# VL53L1X_Winkelplatine.net
KiCad netlist of a schematic drawn in EAGLE
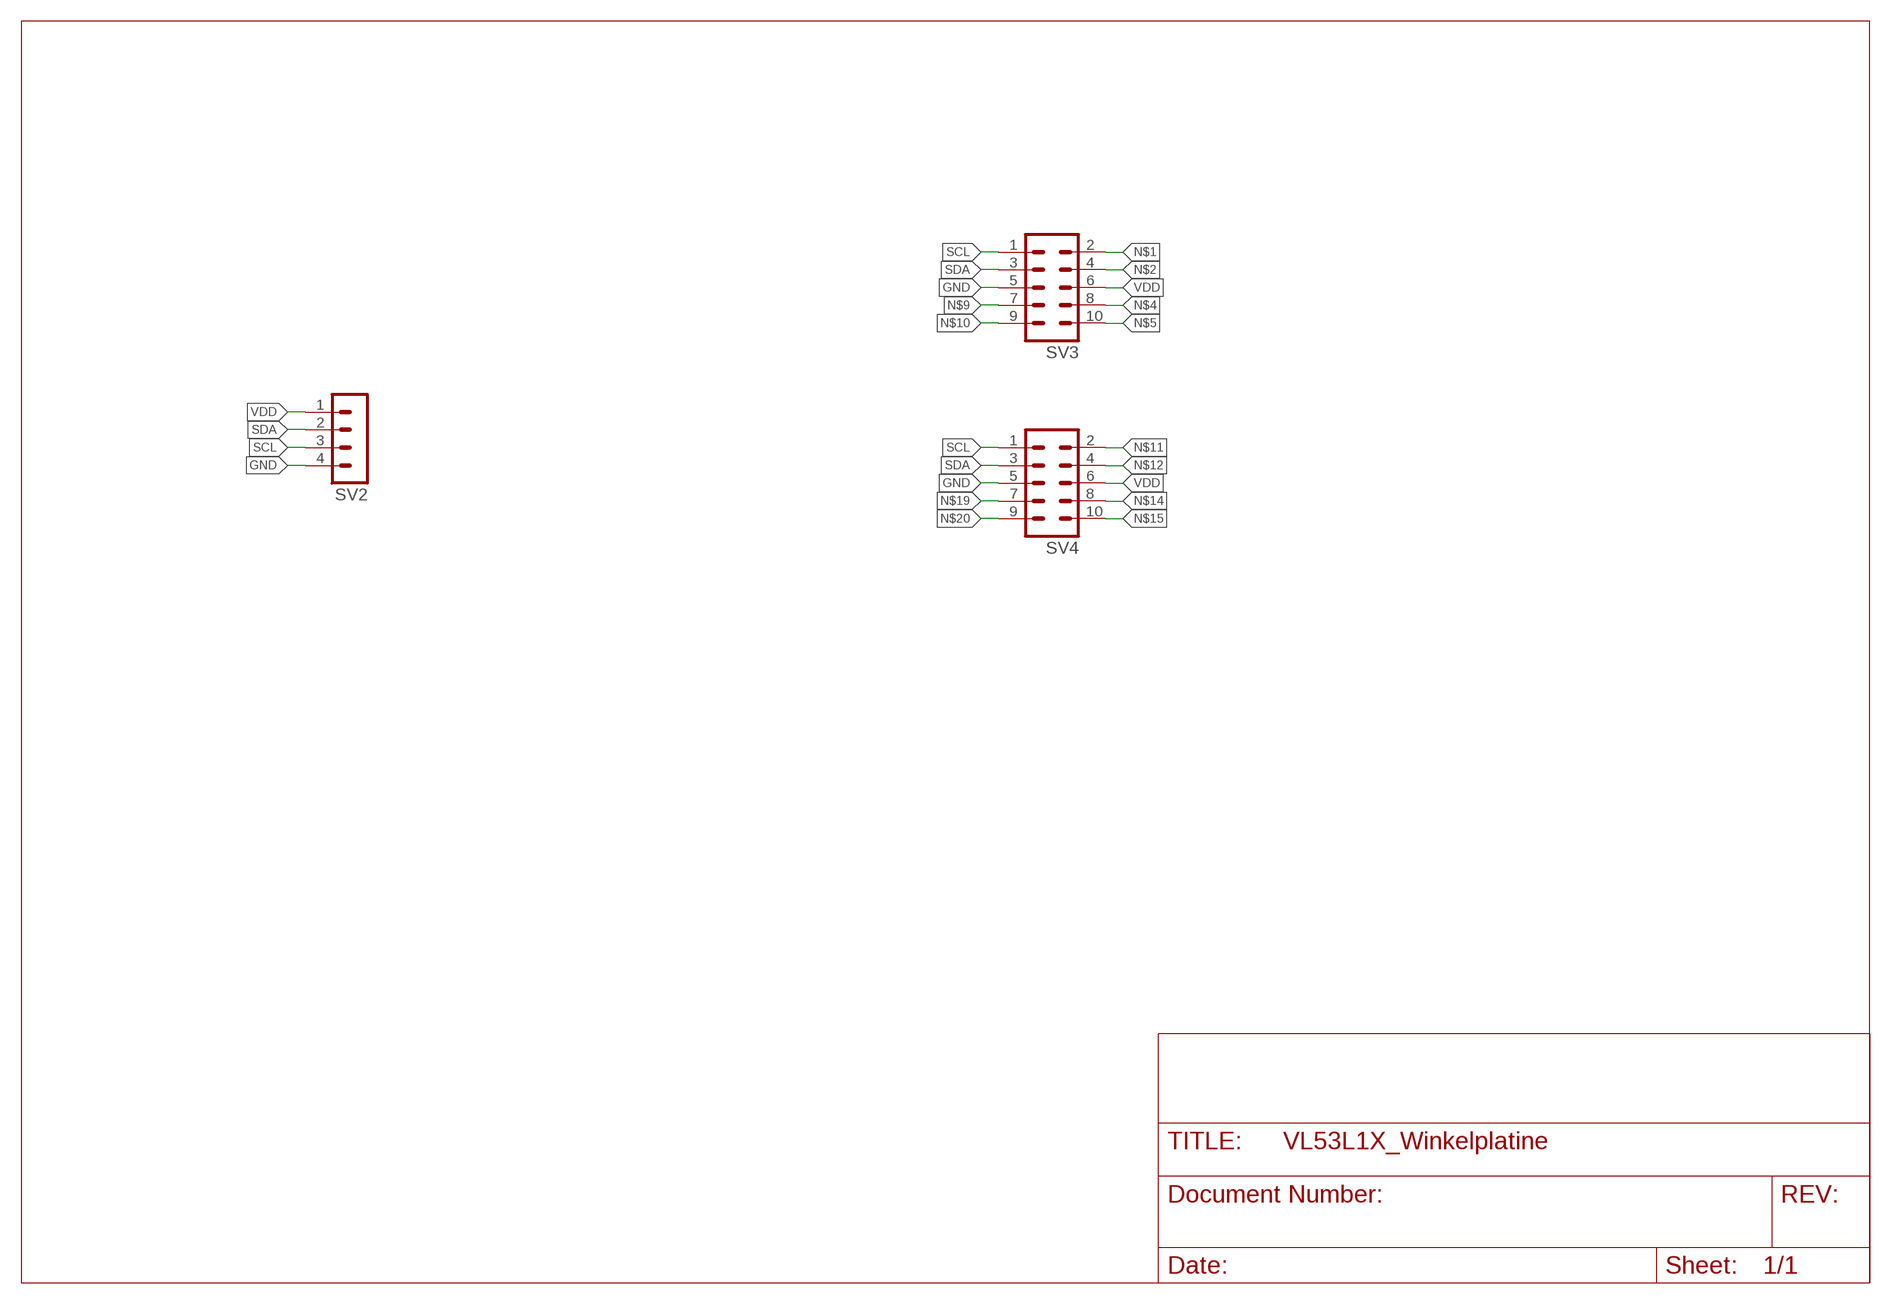
[diagram p0: schematic, sheet 1]

(export (version "E")
  (design (tool "Eeschema 10.0.6"))
  (components
    (comp (ref "SV2")
      (value "MA04-1")
      (footprint "eagle-import:MA04-1")
      (libsource (lib "eagle-import") (part "MA04-1"))
    )
    (comp (ref "SV3")
      (value "MA05-2")
      (footprint "eagle-import:MA05-2")
      (libsource (lib "eagle-import") (part "MA05-2"))
    )
    (comp (ref "SV4")
      (value "MA05-2")
      (footprint "eagle-import:MA05-2")
      (libsource (lib "eagle-import") (part "MA05-2"))
    )
  )
  (nets
    (net (code "1") (name "GND") (class "Default")
      (node (ref "SV2") (pin "4") (pinfunction "4_4") (pintype "passive"))
      (node (ref "SV3") (pin "5") (pinfunction "5_5") (pintype "passive"))
      (node (ref "SV4") (pin "5") (pinfunction "5_5") (pintype "passive"))
    )
    (net (code "2") (name "N$1") (class "Default")
      (node (ref "SV3") (pin "2") (pinfunction "2_2") (pintype "passive"))
    )
    (net (code "3") (name "N$2") (class "Default")
      (node (ref "SV3") (pin "4") (pinfunction "4_4") (pintype "passive"))
    )
    (net (code "4") (name "N$4") (class "Default")
      (node (ref "SV3") (pin "8") (pinfunction "8_8") (pintype "passive"))
    )
    (net (code "5") (name "N$5") (class "Default")
      (node (ref "SV3") (pin "10") (pinfunction "10_10") (pintype "passive"))
    )
    (net (code "6") (name "N$9") (class "Default")
      (node (ref "SV3") (pin "7") (pinfunction "7_7") (pintype "passive"))
    )
    (net (code "7") (name "N$10") (class "Default")
      (node (ref "SV3") (pin "9") (pinfunction "9_9") (pintype "passive"))
    )
    (net (code "8") (name "N$11") (class "Default")
      (node (ref "SV4") (pin "2") (pinfunction "2_2") (pintype "passive"))
    )
    (net (code "9") (name "N$12") (class "Default")
      (node (ref "SV4") (pin "4") (pinfunction "4_4") (pintype "passive"))
    )
    (net (code "10") (name "N$14") (class "Default")
      (node (ref "SV4") (pin "8") (pinfunction "8_8") (pintype "passive"))
    )
    (net (code "11") (name "N$15") (class "Default")
      (node (ref "SV4") (pin "10") (pinfunction "10_10") (pintype "passive"))
    )
    (net (code "12") (name "N$19") (class "Default")
      (node (ref "SV4") (pin "7") (pinfunction "7_7") (pintype "passive"))
    )
    (net (code "13") (name "N$20") (class "Default")
      (node (ref "SV4") (pin "9") (pinfunction "9_9") (pintype "passive"))
    )
    (net (code "14") (name "SCL") (class "Default")
      (node (ref "SV2") (pin "3") (pinfunction "3_3") (pintype "passive"))
      (node (ref "SV3") (pin "1") (pinfunction "1_1") (pintype "passive"))
      (node (ref "SV4") (pin "1") (pinfunction "1_1") (pintype "passive"))
    )
    (net (code "15") (name "SDA") (class "Default")
      (node (ref "SV2") (pin "2") (pinfunction "2_2") (pintype "passive"))
      (node (ref "SV3") (pin "3") (pinfunction "3_3") (pintype "passive"))
      (node (ref "SV4") (pin "3") (pinfunction "3_3") (pintype "passive"))
    )
    (net (code "16") (name "VDD") (class "Default")
      (node (ref "SV2") (pin "1") (pinfunction "1_1") (pintype "passive"))
      (node (ref "SV3") (pin "6") (pinfunction "6_6") (pintype "passive"))
      (node (ref "SV4") (pin "6") (pinfunction "6_6") (pintype "passive"))
    )
  )
)
